# Principal.net
KiCad netlist of a schematic drawn in Altium Designer
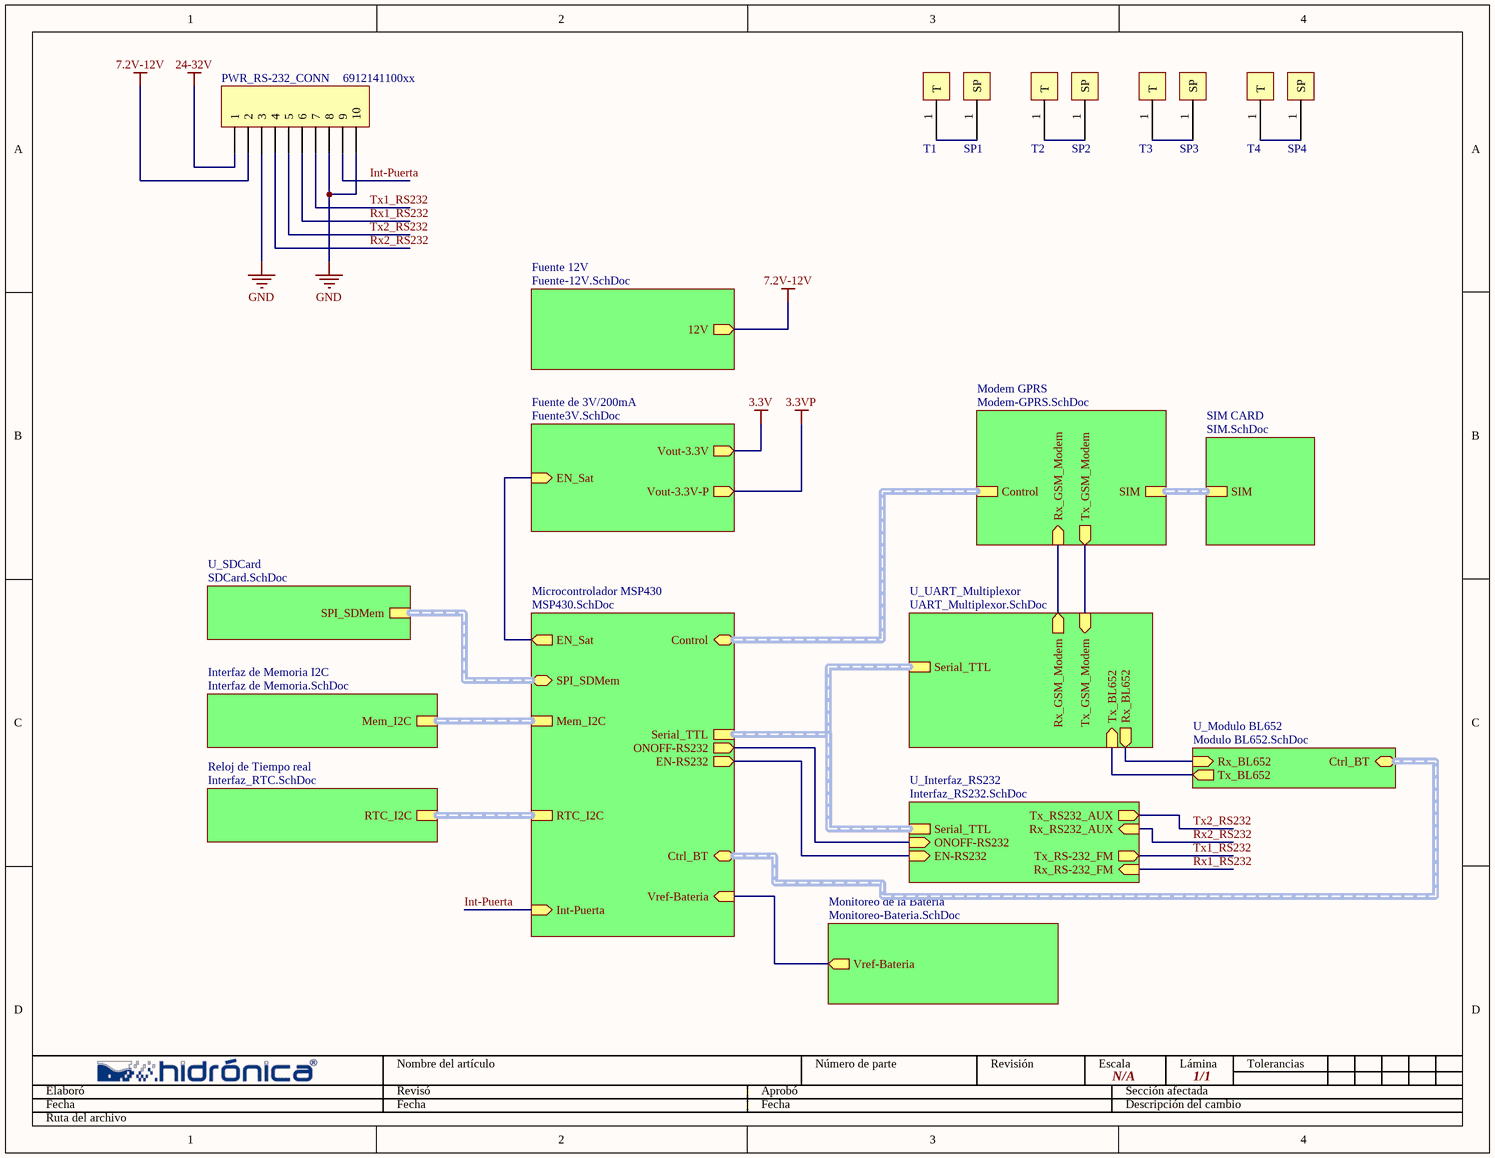
[diagram p0: Principal.SchDoc]

(export (version "E")
  (design (tool "Eeschema 10.0.6"))
  (components
    (comp (ref "PWR_RS-232_CONN")
      (value "6912141100xx")
      (footprint "691214110002x2_691214110003x2")
      (description "10 Position Wire to Board Terminal Block Horizontal with Board 0.200\" (5.08mm) Through Hole")
      (fields
        (field (name "MANUFACTURER") "Wurth Elektronik")
        (field (name "VOLTAGE") "300V")
        (field (name "PUBLISHER") "Altium Limited")
      )
      (libsource (lib "Miscellaneous Connectors") (part "Header 10H"))
    )
    (comp (ref "SP1")
      (value "~")
      (footprint "SPACER")
      (description "No Aplica")
      (libsource (lib "LibreriaEstandar2") (part "PRUEBA"))
    )
    (comp (ref "SP2")
      (value "~")
      (footprint "SPACER")
      (description "No Aplica")
      (libsource (lib "LibreriaEstandar2") (part "PRUEBA"))
    )
    (comp (ref "SP3")
      (value "~")
      (footprint "SPACER")
      (description "No Aplica")
      (libsource (lib "LibreriaEstandar2") (part "PRUEBA"))
    )
    (comp (ref "SP4")
      (value "~")
      (footprint "SPACER")
      (description "No Aplica")
      (libsource (lib "LibreriaEstandar2") (part "PRUEBA"))
    )
    (comp (ref "T1")
      (value "~")
      (footprint "Tornillo")
      (description "No Aplica")
      (libsource (lib "") (part "PRUEBA_1"))
    )
    (comp (ref "T2")
      (value "~")
      (footprint "Tornillo")
      (description "No Aplica")
      (libsource (lib "") (part "PRUEBA_1"))
    )
    (comp (ref "T3")
      (value "~")
      (footprint "Tornillo")
      (description "No Aplica")
      (libsource (lib "") (part "PRUEBA_1"))
    )
    (comp (ref "T4")
      (value "~")
      (footprint "Tornillo")
      (description "No Aplica")
      (libsource (lib "") (part "PRUEBA_1"))
    )
  )
  (nets
    (net (code "5") (name "/Int-Puerta") (class "Default")
      (node (ref "PWR_RS-232_CONN") (pin "9") (pinfunction "9_9") (pintype "passive"))
    )
    (net (code "9") (name "/Rx1_RS232") (class "Default")
      (node (ref "PWR_RS-232_CONN") (pin "6") (pinfunction "6_6") (pintype "passive"))
    )
    (net (code "10") (name "/Rx2_RS232") (class "Default")
      (node (ref "PWR_RS-232_CONN") (pin "4") (pinfunction "4_4") (pintype "passive"))
    )
    (net (code "16") (name "/Tx1_RS232") (class "Default")
      (node (ref "PWR_RS-232_CONN") (pin "7") (pinfunction "7_7") (pintype "passive"))
    )
    (net (code "17") (name "/Tx2_RS232") (class "Default")
      (node (ref "PWR_RS-232_CONN") (pin "5") (pinfunction "5_5") (pintype "passive"))
    )
    (net (code "23") (name "7.2V-12V") (class "Default")
      (node (ref "PWR_RS-232_CONN") (pin "2") (pinfunction "2_2") (pintype "passive"))
    )
    (net (code "24") (name "24-32V") (class "Default")
      (node (ref "PWR_RS-232_CONN") (pin "1") (pinfunction "1_1") (pintype "passive"))
    )
    (net (code "25") (name "GND") (class "Default")
      (node (ref "PWR_RS-232_CONN") (pin "10") (pinfunction "10_10") (pintype "passive"))
      (node (ref "PWR_RS-232_CONN") (pin "3") (pinfunction "3_3") (pintype "passive"))
      (node (ref "PWR_RS-232_CONN") (pin "8") (pinfunction "8_8") (pintype "passive"))
    )
    (net (code "26") (name "Net-(SP1-SP)") (class "Default")
      (node (ref "SP1") (pin "1") (pinfunction "SP_1") (pintype "passive"))
      (node (ref "T1") (pin "1") (pinfunction "T_1") (pintype "passive"))
    )
    (net (code "27") (name "Net-(SP2-SP)") (class "Default")
      (node (ref "SP2") (pin "1") (pinfunction "SP_1") (pintype "passive"))
      (node (ref "T2") (pin "1") (pinfunction "T_1") (pintype "passive"))
    )
    (net (code "28") (name "Net-(SP3-SP)") (class "Default")
      (node (ref "SP3") (pin "1") (pinfunction "SP_1") (pintype "passive"))
      (node (ref "T3") (pin "1") (pinfunction "T_1") (pintype "passive"))
    )
    (net (code "29") (name "Net-(SP4-SP)") (class "Default")
      (node (ref "SP4") (pin "1") (pinfunction "SP_1") (pintype "passive"))
      (node (ref "T4") (pin "1") (pinfunction "T_1") (pintype "passive"))
    )
  )
)
